# FullPower.net
KiCad netlist of a schematic drawn in EAGLE
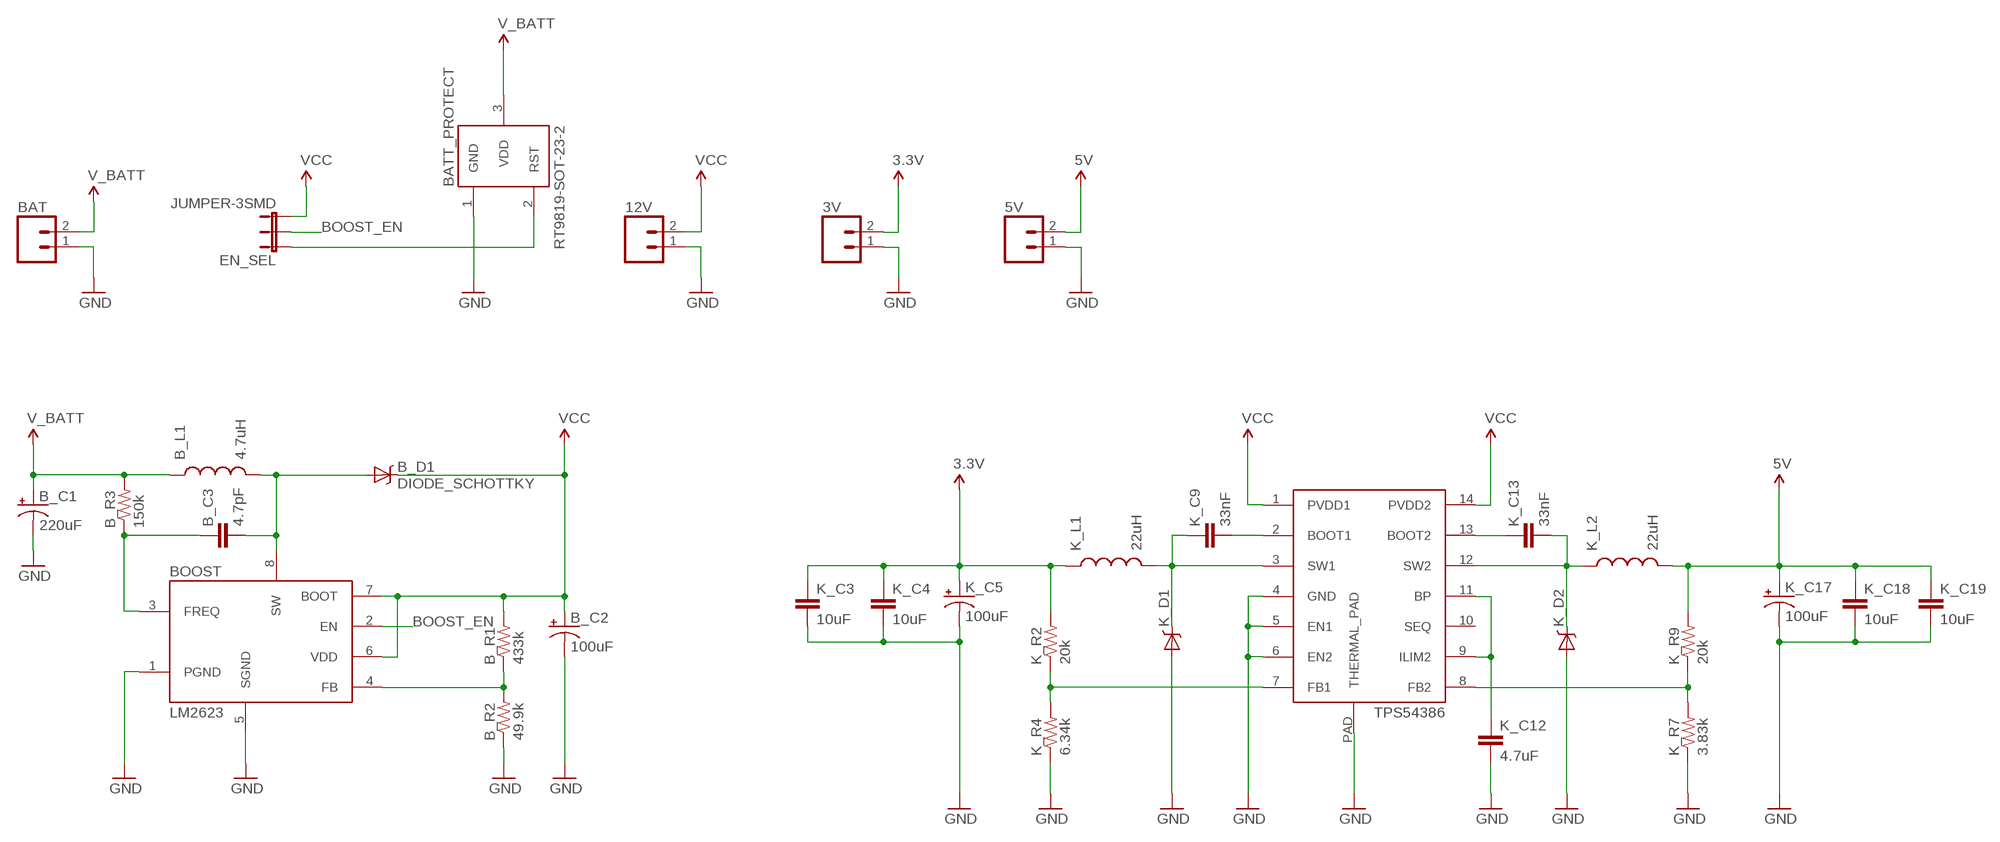
[diagram p0: schematic, sheet 1]

(export (version "E")
  (design (tool "Eeschema 10.0.6"))
  (components
    (comp (ref "3V")
      (value "M02PTH")
      (footprint "eagle-import:1X02")
      (libsource (lib "eagle-import") (part "M02PTH"))
    )
    (comp (ref "5V")
      (value "M02PTH")
      (footprint "eagle-import:1X02")
      (libsource (lib "eagle-import") (part "M02PTH"))
    )
    (comp (ref "12V")
      (value "M02PTH")
      (footprint "eagle-import:1X02")
      (libsource (lib "eagle-import") (part "M02PTH"))
    )
    (comp (ref "BAT")
      (value "M02PTH")
      (footprint "eagle-import:1X02")
      (libsource (lib "eagle-import") (part "M02PTH"))
    )
    (comp (ref "BATT_PROTECT")
      (value "RT9819-SOT-23-2")
      (footprint "eagle-import:SOT-23-2")
      (libsource (lib "eagle-import") (part "RT9819-SOT-23-2"))
    )
    (comp (ref "BOOST")
      (value "LM2623")
      (footprint "eagle-import:MSOP-8")
      (libsource (lib "eagle-import") (part "LM2623-MSOP-8"))
    )
    (comp (ref "BUCK")
      (value "TPS54386")
      (footprint "eagle-import:HTSSOP-14")
      (libsource (lib "eagle-import") (part "TPS54386-HTSSOP-14"))
    )
    (comp (ref "B_C1")
      (value "220uF")
      (footprint "eagle-import:EIA3528")
      (libsource (lib "eagle-import") (part "CAP_POL3528"))
    )
    (comp (ref "B_C2")
      (value "100uF")
      (footprint "eagle-import:EIA7343")
      (libsource (lib "eagle-import") (part "CAP_POL7343"))
    )
    (comp (ref "B_C3")
      (value "4.7pF")
      (footprint "eagle-import:CAP-1608")
      (libsource (lib "eagle-import") (part "CAP_CER-1608(0603)"))
    )
    (comp (ref "B_D1")
      (value "DIODE_SCHOTTKY")
      (footprint "eagle-import:DO-214AB")
      (libsource (lib "eagle-import") (part "DIODE_SCHOTTKY"))
    )
    (comp (ref "B_L1")
      (value "4.7uH")
      (footprint "eagle-import:INDUCTOR_SRR7032")
      (libsource (lib "eagle-import") (part "INDUCTOR-SRR7032"))
    )
    (comp (ref "B_R1")
      (value "433k")
      (footprint "eagle-import:0805")
      (libsource (lib "eagle-import") (part "RESISTOR0805-RES"))
    )
    (comp (ref "B_R2")
      (value "49.9k")
      (footprint "eagle-import:0805")
      (libsource (lib "eagle-import") (part "RESISTOR0805-RES"))
    )
    (comp (ref "B_R3")
      (value "150k")
      (footprint "eagle-import:0805")
      (libsource (lib "eagle-import") (part "RESISTOR0805-RES"))
    )
    (comp (ref "EN_SEL")
      (value "JUMPER-3SMD")
      (footprint "eagle-import:SJ_3")
      (libsource (lib "eagle-import") (part "JUMPER-3SMD"))
    )
    (comp (ref "K_C3")
      (value "10uF")
      (footprint "eagle-import:CAP-2012")
      (libsource (lib "eagle-import") (part "CAP_CER-2012(0805)"))
    )
    (comp (ref "K_C4")
      (value "10uF")
      (footprint "eagle-import:CAP-2012")
      (libsource (lib "eagle-import") (part "CAP_CER-2012(0805)"))
    )
    (comp (ref "K_C5")
      (value "100uF")
      (footprint "eagle-import:PANASONIC-F")
      (libsource (lib "eagle-import") (part "CAP_POL-PANASONIC-F"))
    )
    (comp (ref "K_C9")
      (value "33nF")
      (footprint "eagle-import:CAP-1608")
      (libsource (lib "eagle-import") (part "CAP_CER-1608(0603)"))
    )
    (comp (ref "K_C12")
      (value "4.7uF")
      (footprint "eagle-import:CAP-2012")
      (libsource (lib "eagle-import") (part "CAP_CER-2012(0805)"))
    )
    (comp (ref "K_C13")
      (value "33nF")
      (footprint "eagle-import:CAP-1608")
      (libsource (lib "eagle-import") (part "CAP_CER-1608(0603)"))
    )
    (comp (ref "K_C17")
      (value "100uF")
      (footprint "eagle-import:PANASONIC-F")
      (libsource (lib "eagle-import") (part "CAP_POL-PANASONIC-F"))
    )
    (comp (ref "K_C18")
      (value "10uF")
      (footprint "eagle-import:CAP-2012")
      (libsource (lib "eagle-import") (part "CAP_CER-2012(0805)"))
    )
    (comp (ref "K_C19")
      (value "10uF")
      (footprint "eagle-import:CAP-2012")
      (libsource (lib "eagle-import") (part "CAP_CER-2012(0805)"))
    )
    (comp (ref "K_D1")
      (value "DIODE_SCHOTTKY")
      (footprint "eagle-import:DO-214AB")
      (libsource (lib "eagle-import") (part "DIODE_SCHOTTKY"))
    )
    (comp (ref "K_D2")
      (value "DIODE_SCHOTTKY")
      (footprint "eagle-import:DO-214AB")
      (libsource (lib "eagle-import") (part "DIODE_SCHOTTKY"))
    )
    (comp (ref "K_L1")
      (value "22uH")
      (footprint "eagle-import:INDUCTOR-PF0560NL")
      (libsource (lib "eagle-import") (part "INDUCTOR-PF0560"))
    )
    (comp (ref "K_L2")
      (value "22uH")
      (footprint "eagle-import:INDUCTOR-PF0560NL")
      (libsource (lib "eagle-import") (part "INDUCTOR-PF0560"))
    )
    (comp (ref "K_R2")
      (value "20k")
      (footprint "eagle-import:0805")
      (libsource (lib "eagle-import") (part "RESISTOR0805-RES"))
    )
    (comp (ref "K_R4")
      (value "6.34k")
      (footprint "eagle-import:0805")
      (libsource (lib "eagle-import") (part "RESISTOR0805-RES"))
    )
    (comp (ref "K_R7")
      (value "3.83k")
      (footprint "eagle-import:0805")
      (libsource (lib "eagle-import") (part "RESISTOR0805-RES"))
    )
    (comp (ref "K_R9")
      (value "20k")
      (footprint "eagle-import:0805")
      (libsource (lib "eagle-import") (part "RESISTOR0805-RES"))
    )
  )
  (nets
    (net (code "1") (name "/BOOST_EN") (class "Default")
      (node (ref "BOOST") (pin "2") (pinfunction "EN_2") (pintype "bidirectional"))
      (node (ref "EN_SEL") (pin "2") (pinfunction "2_2") (pintype "passive"))
    )
    (net (code "2") (name "3.3V") (class "Default")
      (node (ref "3V") (pin "2") (pinfunction "2_2") (pintype "passive"))
      (node (ref "K_C3") (pin "+") (pinfunction "+_+") (pintype "passive"))
      (node (ref "K_C4") (pin "+") (pinfunction "+_+") (pintype "passive"))
      (node (ref "K_C5") (pin "+") (pinfunction "+_+") (pintype "passive"))
      (node (ref "K_L1") (pin "2") (pinfunction "2_2") (pintype "passive"))
      (node (ref "K_R2") (pin "2") (pinfunction "2_2") (pintype "passive"))
    )
    (net (code "3") (name "5V") (class "Default")
      (node (ref "5V") (pin "2") (pinfunction "2_2") (pintype "passive"))
      (node (ref "K_C17") (pin "+") (pinfunction "+_+") (pintype "passive"))
      (node (ref "K_C18") (pin "+") (pinfunction "+_+") (pintype "passive"))
      (node (ref "K_C19") (pin "+") (pinfunction "+_+") (pintype "passive"))
      (node (ref "K_L2") (pin "1") (pinfunction "1_1") (pintype "passive"))
      (node (ref "K_R9") (pin "2") (pinfunction "2_2") (pintype "passive"))
    )
    (net (code "4") (name "GND") (class "Default")
      (node (ref "12V") (pin "1") (pinfunction "1_1") (pintype "passive"))
      (node (ref "3V") (pin "1") (pinfunction "1_1") (pintype "passive"))
      (node (ref "5V") (pin "1") (pinfunction "1_1") (pintype "passive"))
      (node (ref "BAT") (pin "1") (pinfunction "1_1") (pintype "passive"))
      (node (ref "BATT_PROTECT") (pin "1") (pinfunction "GND_1") (pintype "bidirectional"))
      (node (ref "BOOST") (pin "1") (pinfunction "PGND_1") (pintype "bidirectional"))
      (node (ref "BOOST") (pin "5") (pinfunction "SGND_5") (pintype "bidirectional"))
      (node (ref "BUCK") (pin "4") (pinfunction "GND_4") (pintype "bidirectional"))
      (node (ref "BUCK") (pin "5") (pinfunction "EN1_5") (pintype "bidirectional"))
      (node (ref "BUCK") (pin "6") (pinfunction "EN2_6") (pintype "bidirectional"))
      (node (ref "BUCK") (pin "PAD") (pinfunction "THERMAL_PAD_PAD") (pintype "bidirectional"))
      (node (ref "B_C1") (pin "C") (pinfunction "-_C") (pintype "passive"))
      (node (ref "B_C2") (pin "C") (pinfunction "-_C") (pintype "passive"))
      (node (ref "B_R2") (pin "1") (pinfunction "1_1") (pintype "passive"))
      (node (ref "K_C12") (pin "-") (pinfunction "-_-") (pintype "passive"))
      (node (ref "K_C17") (pin "-") (pinfunction "-_-") (pintype "passive"))
      (node (ref "K_C18") (pin "-") (pinfunction "-_-") (pintype "passive"))
      (node (ref "K_C19") (pin "-") (pinfunction "-_-") (pintype "passive"))
      (node (ref "K_C3") (pin "-") (pinfunction "-_-") (pintype "passive"))
      (node (ref "K_C4") (pin "-") (pinfunction "-_-") (pintype "passive"))
      (node (ref "K_C5") (pin "-") (pinfunction "-_-") (pintype "passive"))
      (node (ref "K_D1") (pin "A") (pinfunction "A_A") (pintype "passive"))
      (node (ref "K_D2") (pin "A") (pinfunction "A_A") (pintype "passive"))
      (node (ref "K_R4") (pin "1") (pinfunction "1_1") (pintype "passive"))
      (node (ref "K_R7") (pin "1") (pinfunction "1_1") (pintype "passive"))
    )
    (net (code "5") (name "Net-(BATT_PROTECT-RST)") (class "Default")
      (node (ref "BATT_PROTECT") (pin "2") (pinfunction "RST_2") (pintype "bidirectional"))
      (node (ref "EN_SEL") (pin "1") (pinfunction "1_1") (pintype "passive"))
    )
    (net (code "6") (name "Net-(BOOST-FB)") (class "Default")
      (node (ref "BOOST") (pin "4") (pinfunction "FB_4") (pintype "bidirectional"))
      (node (ref "B_R1") (pin "1") (pinfunction "1_1") (pintype "passive"))
      (node (ref "B_R2") (pin "2") (pinfunction "2_2") (pintype "passive"))
    )
    (net (code "7") (name "Net-(BOOST-FREQ)") (class "Default")
      (node (ref "BOOST") (pin "3") (pinfunction "FREQ_3") (pintype "bidirectional"))
      (node (ref "B_C3") (pin "+") (pinfunction "+_+") (pintype "passive"))
      (node (ref "B_R3") (pin "1") (pinfunction "1_1") (pintype "passive"))
    )
    (net (code "8") (name "Net-(BOOST-SW)") (class "Default")
      (node (ref "BOOST") (pin "8") (pinfunction "SW_8") (pintype "bidirectional"))
      (node (ref "B_C3") (pin "-") (pinfunction "-_-") (pintype "passive"))
      (node (ref "B_D1") (pin "A") (pinfunction "A_A") (pintype "passive"))
      (node (ref "B_L1") (pin "1") (pinfunction "1_1") (pintype "passive"))
    )
    (net (code "9") (name "Net-(BUCK-BOOT1)") (class "Default")
      (node (ref "BUCK") (pin "2") (pinfunction "BOOT1_2") (pintype "bidirectional"))
      (node (ref "K_C9") (pin "-") (pinfunction "-_-") (pintype "passive"))
    )
    (net (code "10") (name "Net-(BUCK-BOOT2)") (class "Default")
      (node (ref "BUCK") (pin "13") (pinfunction "BOOT2_13") (pintype "bidirectional"))
      (node (ref "K_C13") (pin "+") (pinfunction "+_+") (pintype "passive"))
    )
    (net (code "11") (name "Net-(BUCK-BP)") (class "Default")
      (node (ref "BUCK") (pin "11") (pinfunction "BP_11") (pintype "bidirectional"))
      (node (ref "BUCK") (pin "9") (pinfunction "ILIM2_9") (pintype "bidirectional"))
      (node (ref "K_C12") (pin "+") (pinfunction "+_+") (pintype "passive"))
    )
    (net (code "12") (name "Net-(BUCK-FB1)") (class "Default")
      (node (ref "BUCK") (pin "7") (pinfunction "FB1_7") (pintype "bidirectional"))
      (node (ref "K_R2") (pin "1") (pinfunction "1_1") (pintype "passive"))
      (node (ref "K_R4") (pin "2") (pinfunction "2_2") (pintype "passive"))
    )
    (net (code "13") (name "Net-(BUCK-FB2)") (class "Default")
      (node (ref "BUCK") (pin "8") (pinfunction "FB2_8") (pintype "bidirectional"))
      (node (ref "K_R7") (pin "2") (pinfunction "2_2") (pintype "passive"))
      (node (ref "K_R9") (pin "1") (pinfunction "1_1") (pintype "passive"))
    )
    (net (code "14") (name "Net-(BUCK-SW1)") (class "Default")
      (node (ref "BUCK") (pin "3") (pinfunction "SW1_3") (pintype "bidirectional"))
      (node (ref "K_C9") (pin "+") (pinfunction "+_+") (pintype "passive"))
      (node (ref "K_D1") (pin "C") (pinfunction "C_C") (pintype "passive"))
      (node (ref "K_L1") (pin "1") (pinfunction "1_1") (pintype "passive"))
    )
    (net (code "15") (name "Net-(BUCK-SW2)") (class "Default")
      (node (ref "BUCK") (pin "12") (pinfunction "SW2_12") (pintype "bidirectional"))
      (node (ref "K_C13") (pin "-") (pinfunction "-_-") (pintype "passive"))
      (node (ref "K_D2") (pin "C") (pinfunction "C_C") (pintype "passive"))
      (node (ref "K_L2") (pin "2") (pinfunction "2_2") (pintype "passive"))
    )
    (net (code "16") (name "VCC") (class "Default")
      (node (ref "12V") (pin "2") (pinfunction "2_2") (pintype "passive"))
      (node (ref "BOOST") (pin "6") (pinfunction "VDD_6") (pintype "bidirectional"))
      (node (ref "BOOST") (pin "7") (pinfunction "BOOT_7") (pintype "bidirectional"))
      (node (ref "BUCK") (pin "1") (pinfunction "PVDD1_1") (pintype "bidirectional"))
      (node (ref "BUCK") (pin "14") (pinfunction "PVDD2_14") (pintype "bidirectional"))
      (node (ref "B_C2") (pin "A") (pinfunction "+_A") (pintype "passive"))
      (node (ref "B_D1") (pin "C") (pinfunction "C_C") (pintype "passive"))
      (node (ref "B_R1") (pin "2") (pinfunction "2_2") (pintype "passive"))
      (node (ref "EN_SEL") (pin "3") (pinfunction "3_3") (pintype "passive"))
    )
    (net (code "17") (name "V_BATT") (class "Default")
      (node (ref "BAT") (pin "2") (pinfunction "2_2") (pintype "passive"))
      (node (ref "BATT_PROTECT") (pin "3") (pinfunction "VDD_3") (pintype "bidirectional"))
      (node (ref "B_C1") (pin "A") (pinfunction "+_A") (pintype "passive"))
      (node (ref "B_L1") (pin "2") (pinfunction "2_2") (pintype "passive"))
      (node (ref "B_R3") (pin "2") (pinfunction "2_2") (pintype "passive"))
    )
    (net (code "18") (name "unconnected-(BUCK-SEQ-Pad10)") (class "Default")
      (node (ref "BUCK") (pin "10") (pinfunction "SEQ_10") (pintype "bidirectional"))
    )
  )
)
